# sensor-hum-temp.net
KiCad netlist of a schematic drawn in Altium Designer
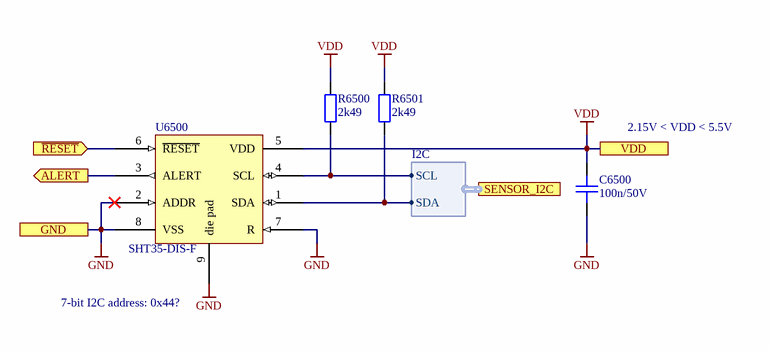
[diagram p0: sensor-hum-temp.SchDoc]

(export (version "E")
  (design (tool "Eeschema 10.0.6"))
  (components
    (comp (ref "C6500")
      (value "100n/50V")
      (footprint "CAPC1005X06N")
      (description "MLCC")
      (fields (field (name "PART NUMBER") "gen_C_ceramic_100n_50V_X7R_0402"))
      (libsource (lib "OE750") (part "C"))
    )
    (comp (ref "R6500")
      (value "2k49")
      (footprint "RESC1005X04N")
      (description "SMD Resistor 2k49 0402")
      (fields (field (name "PART NUMBER") "gen_R_2k49_0402") (field (name "TOLERANCE") "1%"))
      (libsource (lib "OE750") (part "R"))
    )
    (comp (ref "R6501")
      (value "2k49")
      (footprint "RESC1005X04N")
      (description "SMD Resistor 2k49 0402")
      (fields (field (name "PART NUMBER") "gen_R_2k49_0402") (field (name "TOLERANCE") "1%"))
      (libsource (lib "OE750") (part "R"))
    )
    (comp (ref "U6500")
      (value "SHT35-DIS-F")
      (footprint "SHT3X")
      (description "Humidity/Temp Sensor, Digital, Dfn-8")
      (fields (field (name "MANUFACTURER") "Sensirion"))
      (libsource (lib "OE750") (part "SHT3x-DIS"))
    )
  )
  (nets
    (net (code "2") (name "/ALERT") (class "Default")
      (node (ref "U6500") (pin "3") (pinfunction "ALERT_3") (pintype "output"))
    )
    (net (code "3") (name "/RESET") (class "Default")
      (node (ref "U6500") (pin "6") (pinfunction "~{RESET}_6") (pintype "input"))
    )
    (net (code "5") (name "GND") (class "Default")
      (node (ref "C6500") (pin "1") (pinfunction "1_1") (pintype "passive"))
      (node (ref "U6500") (pin "2") (pinfunction "ADDR_2") (pintype "input"))
      (node (ref "U6500") (pin "7") (pinfunction "R_7") (pintype "input"))
      (node (ref "U6500") (pin "8") (pinfunction "VSS_8") (pintype "power_in"))
      (node (ref "U6500") (pin "9") (pinfunction "die_pad_9") (pintype "power_in"))
    )
    (net (code "6") (name "Net-(U6500-SCL)") (class "Default")
      (node (ref "R6500") (pin "1") (pinfunction "1_1") (pintype "passive"))
      (node (ref "U6500") (pin "4") (pinfunction "SCL_4") (pintype "bidirectional"))
    )
    (net (code "7") (name "Net-(U6500-SDA)") (class "Default")
      (node (ref "R6501") (pin "1") (pinfunction "1_1") (pintype "passive"))
      (node (ref "U6500") (pin "1") (pinfunction "SDA_1") (pintype "bidirectional"))
    )
    (net (code "8") (name "VDD") (class "Default")
      (node (ref "C6500") (pin "2") (pinfunction "2_2") (pintype "passive"))
      (node (ref "R6500") (pin "2") (pinfunction "2_2") (pintype "passive"))
      (node (ref "R6501") (pin "2") (pinfunction "2_2") (pintype "passive"))
      (node (ref "U6500") (pin "5") (pinfunction "VDD_5") (pintype "power_in"))
    )
  )
)
